# prc1000.net
KiCad netlist of a schematic drawn in EAGLE
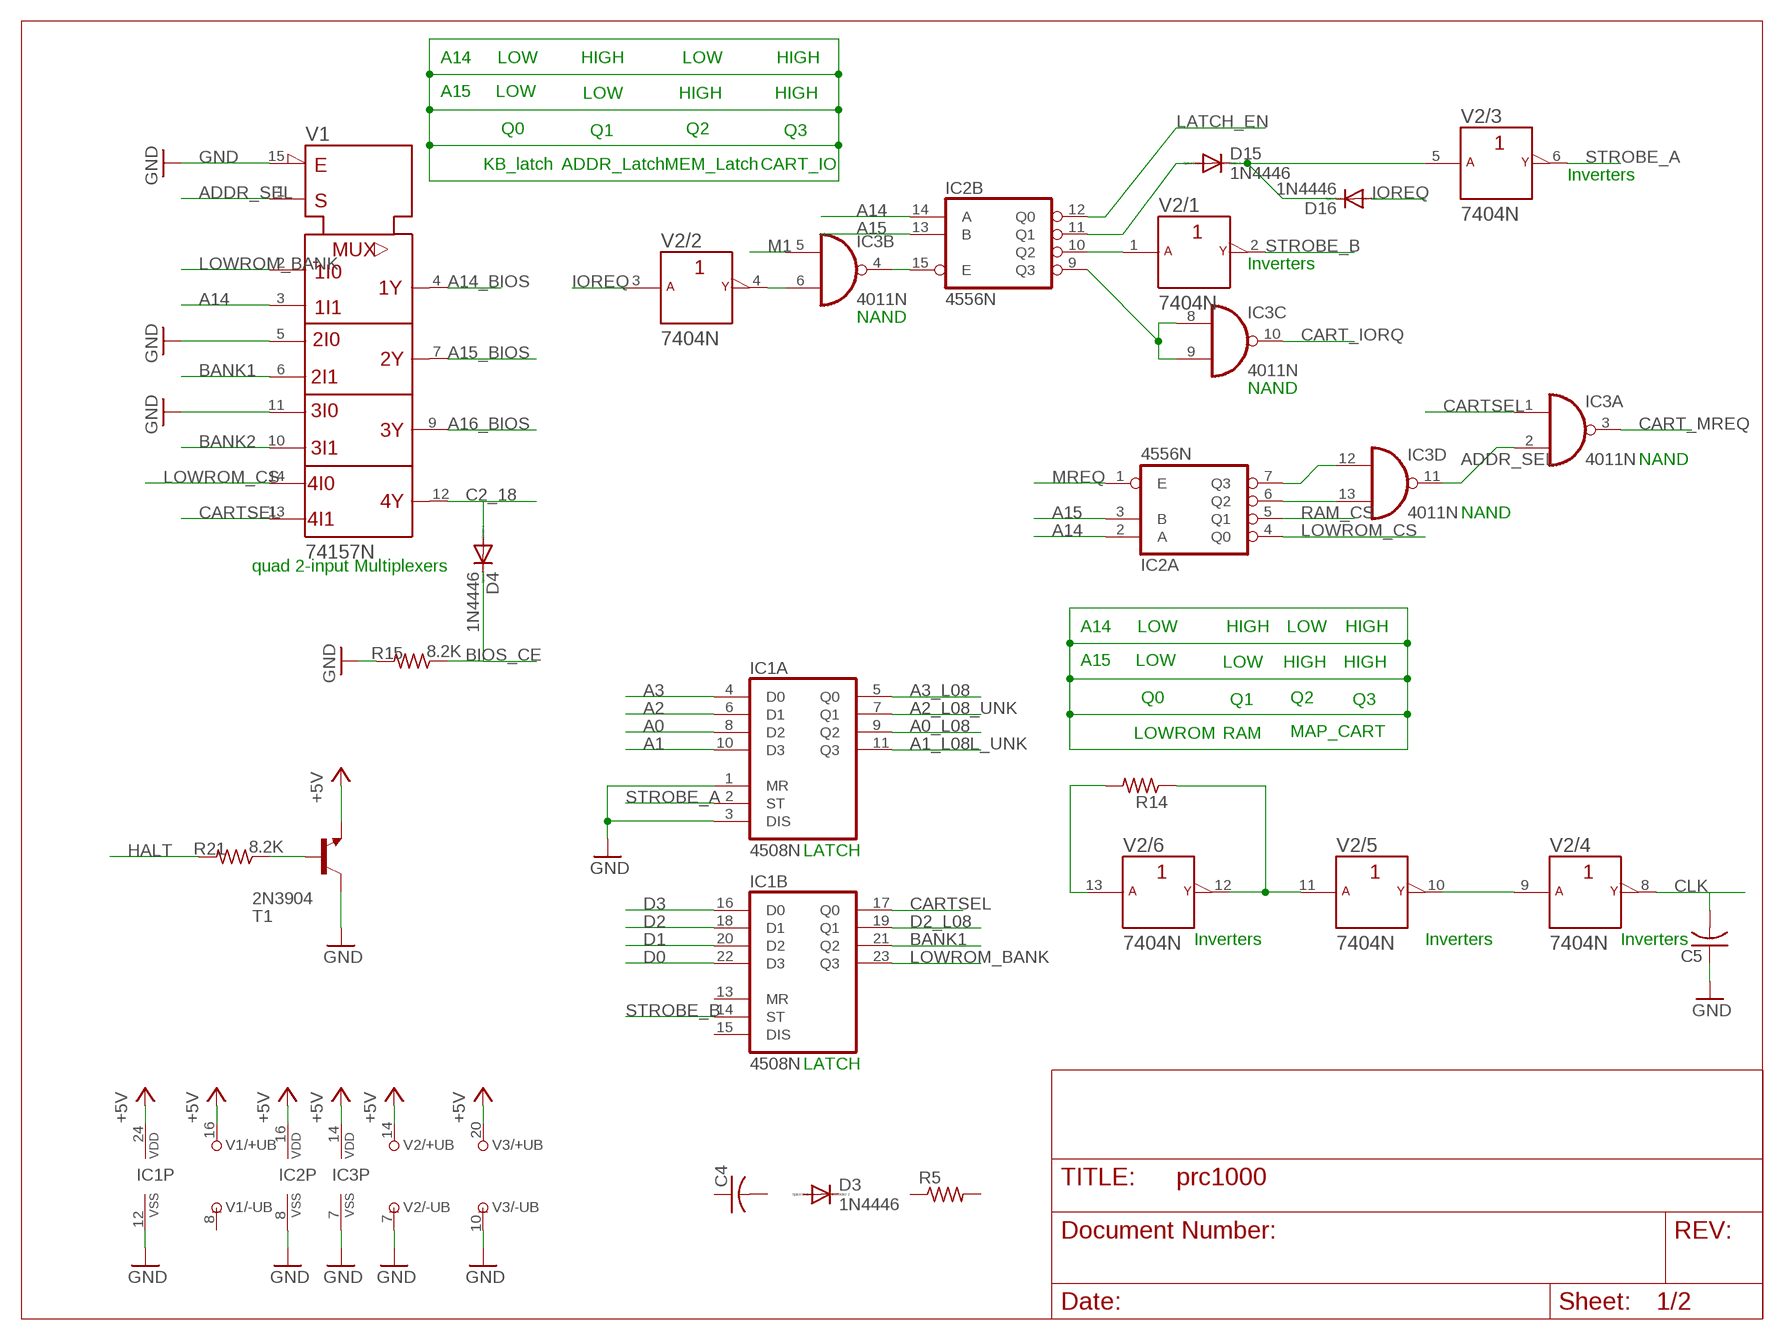
[diagram p0: schematic, sheet 1]
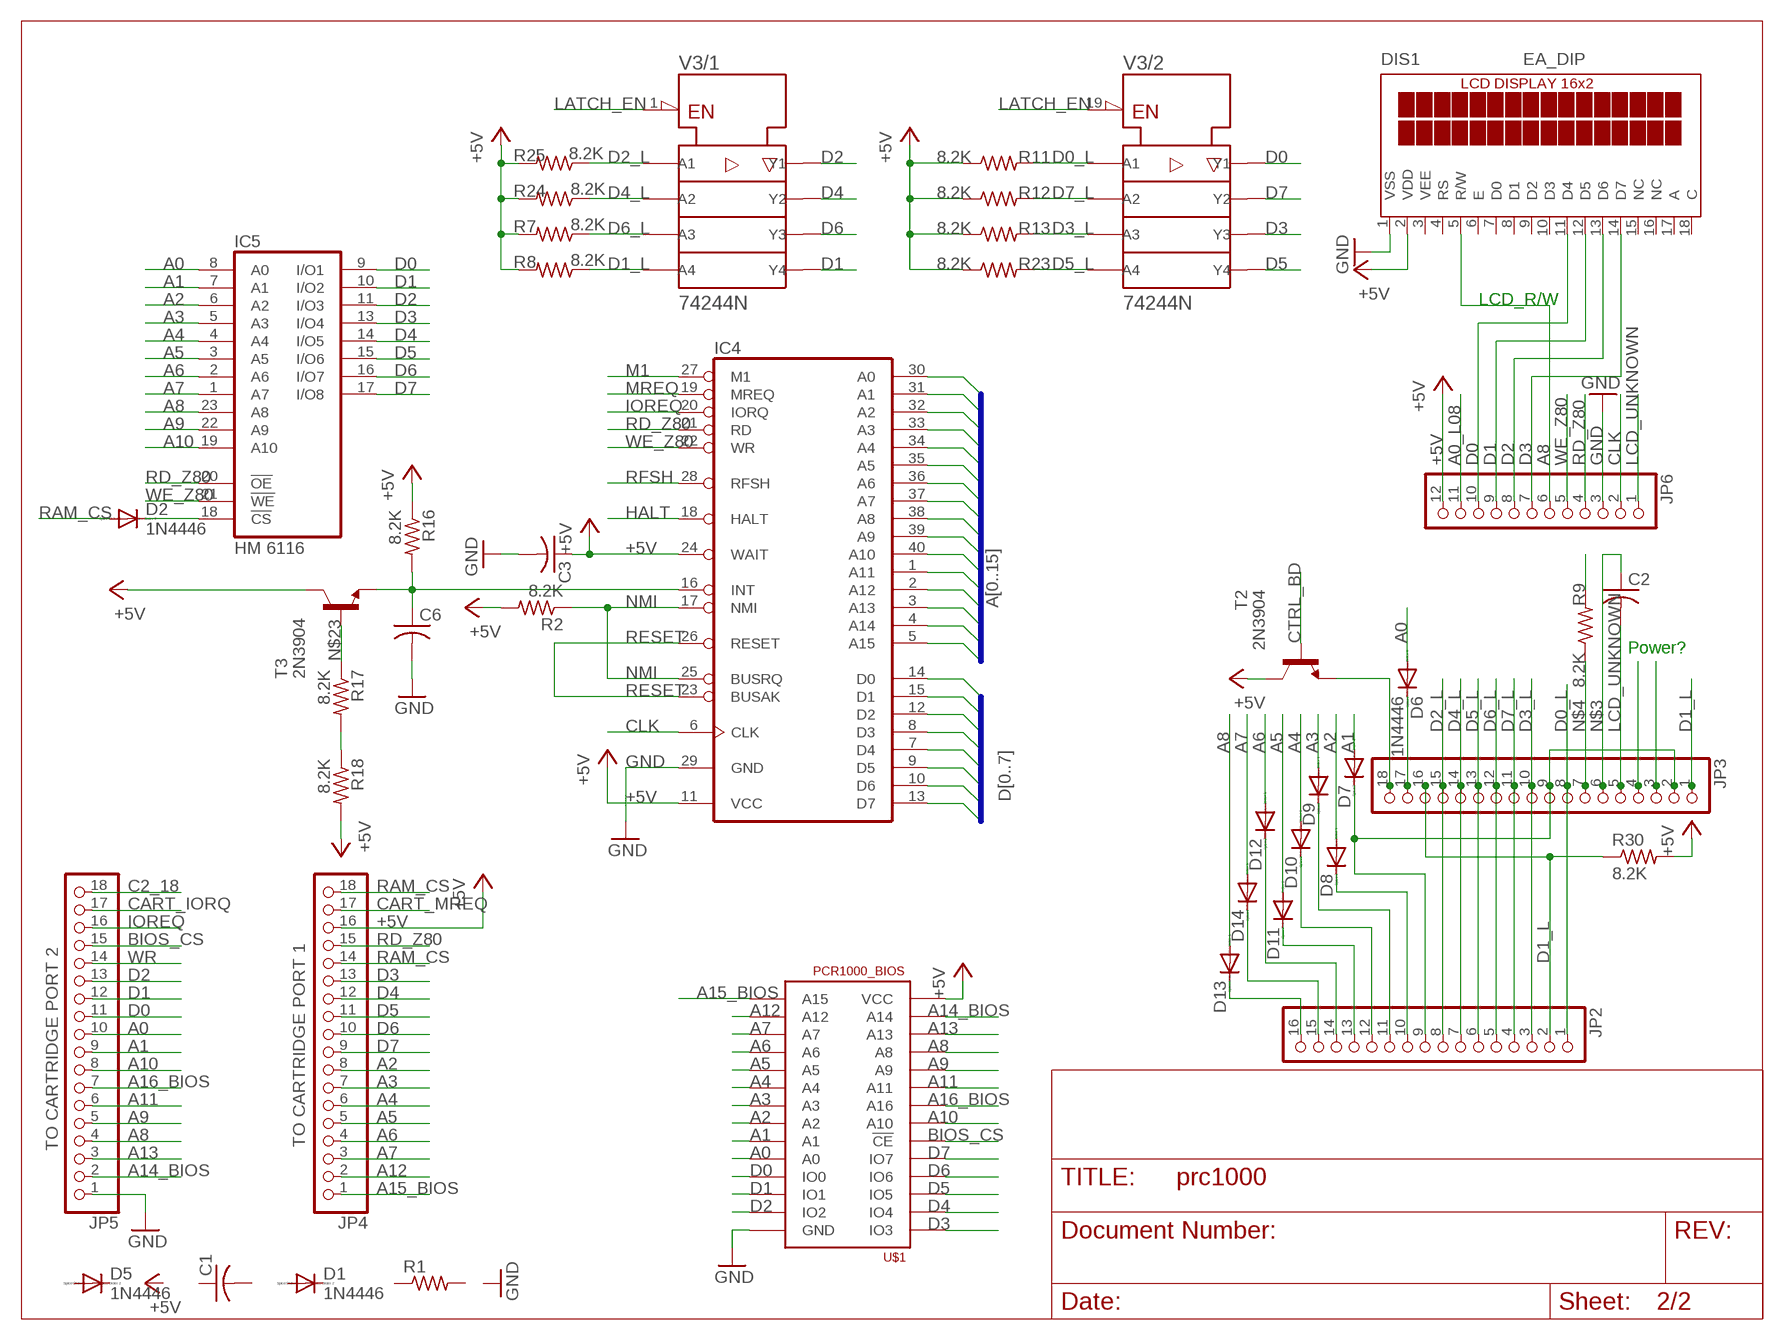
[diagram p1: schematic, sheet 2]

(export (version "E")
  (design (tool "Eeschema 10.0.6"))
  (components
    (comp (ref "C1")
      (value "C-US050-030X075")
      (footprint "eagle-import:C050-030X075")
      (libsource (lib "eagle-import") (part "C-US050-030X075"))
    )
    (comp (ref "C2")
      (value "C-US050-030X075")
      (footprint "eagle-import:C050-030X075")
      (libsource (lib "eagle-import") (part "C-US050-030X075"))
    )
    (comp (ref "C3")
      (value "C-US050-030X075")
      (footprint "eagle-import:C050-030X075")
      (libsource (lib "eagle-import") (part "C-US050-030X075"))
    )
    (comp (ref "C6")
      (value "C-US050-030X075")
      (footprint "eagle-import:C050-030X075")
      (libsource (lib "eagle-import") (part "C-US050-030X075"))
    )
    (comp (ref "D1")
      (value "1N4446")
      (footprint "eagle-import:DO35-10")
      (libsource (lib "eagle-import") (part "1N4446"))
    )
    (comp (ref "D2")
      (value "1N4446")
      (footprint "eagle-import:DO35-10")
      (libsource (lib "eagle-import") (part "1N4446"))
    )
    (comp (ref "D5")
      (value "1N4446")
      (footprint "eagle-import:DO35-10")
      (libsource (lib "eagle-import") (part "1N4446"))
    )
    (comp (ref "D6")
      (value "1N4446")
      (footprint "eagle-import:DO35-10")
      (libsource (lib "eagle-import") (part "1N4446"))
    )
    (comp (ref "D7")
      (value "1N4446")
      (footprint "eagle-import:DO35-10")
      (libsource (lib "eagle-import") (part "1N4446"))
    )
    (comp (ref "D8")
      (value "1N4446")
      (footprint "eagle-import:DO35-10")
      (libsource (lib "eagle-import") (part "1N4446"))
    )
    (comp (ref "D9")
      (value "1N4446")
      (footprint "eagle-import:DO35-10")
      (libsource (lib "eagle-import") (part "1N4446"))
    )
    (comp (ref "D10")
      (value "1N4446")
      (footprint "eagle-import:DO35-10")
      (libsource (lib "eagle-import") (part "1N4446"))
    )
    (comp (ref "D11")
      (value "1N4446")
      (footprint "eagle-import:DO35-10")
      (libsource (lib "eagle-import") (part "1N4446"))
    )
    (comp (ref "D12")
      (value "1N4446")
      (footprint "eagle-import:DO35-10")
      (libsource (lib "eagle-import") (part "1N4446"))
    )
    (comp (ref "D13")
      (value "1N4446")
      (footprint "eagle-import:DO35-10")
      (libsource (lib "eagle-import") (part "1N4446"))
    )
    (comp (ref "D14")
      (value "1N4446")
      (footprint "eagle-import:DO35-10")
      (libsource (lib "eagle-import") (part "1N4446"))
    )
    (comp (ref "DIS1")
      (value "EA_DIP")
      (footprint "eagle-import:EA_DIP")
      (libsource (lib "eagle-import") (part "EA_DIP"))
    )
    (comp (ref "IC4")
      (value "Z80CPU")
      (footprint "eagle-import:DIL40")
      (libsource (lib "eagle-import") (part "Z80CPU"))
    )
    (comp (ref "IC5")
      (value "HM 6116")
      (footprint "eagle-import:DIL24-6")
      (libsource (lib "eagle-import") (part "6116P"))
    )
    (comp (ref "JP2")
      (value "PINHD-1X16")
      (footprint "eagle-import:1X16")
      (libsource (lib "eagle-import") (part "PINHD-1X16"))
    )
    (comp (ref "JP3")
      (value "PINHD-1X18")
      (footprint "eagle-import:1X18")
      (libsource (lib "eagle-import") (part "PINHD-1X18"))
    )
    (comp (ref "JP4")
      (value "TO CARTRIDGE PORT 1")
      (footprint "eagle-import:1X18")
      (libsource (lib "eagle-import") (part "PINHD-1X18"))
    )
    (comp (ref "JP5")
      (value "TO CARTRIDGE PORT 2")
      (footprint "eagle-import:1X18")
      (libsource (lib "eagle-import") (part "PINHD-1X18"))
    )
    (comp (ref "JP6")
      (value "PINHD-1X12")
      (footprint "eagle-import:1X12")
      (libsource (lib "eagle-import") (part "PINHD-1X12"))
    )
    (comp (ref "R1")
      (value "R-US_0207/10")
      (footprint "eagle-import:0207_10")
      (libsource (lib "eagle-import") (part "R-US_0207/10"))
    )
    (comp (ref "R2")
      (value "8.2K")
      (footprint "eagle-import:0207_10")
      (libsource (lib "eagle-import") (part "R-US_0207/10"))
    )
    (comp (ref "R7")
      (value "8.2K")
      (footprint "eagle-import:0207_10")
      (libsource (lib "eagle-import") (part "R-US_0207/10"))
    )
    (comp (ref "R8")
      (value "8.2K")
      (footprint "eagle-import:0207_10")
      (libsource (lib "eagle-import") (part "R-US_0207/10"))
    )
    (comp (ref "R9")
      (value "8.2K")
      (footprint "eagle-import:0207_10")
      (libsource (lib "eagle-import") (part "R-US_0207/10"))
    )
    (comp (ref "R11")
      (value "8.2K")
      (footprint "eagle-import:0207_10")
      (libsource (lib "eagle-import") (part "R-US_0207/10"))
    )
    (comp (ref "R12")
      (value "8.2K")
      (footprint "eagle-import:0207_10")
      (libsource (lib "eagle-import") (part "R-US_0207/10"))
    )
    (comp (ref "R13")
      (value "8.2K")
      (footprint "eagle-import:0207_10")
      (libsource (lib "eagle-import") (part "R-US_0207/10"))
    )
    (comp (ref "R16")
      (value "8.2K")
      (footprint "eagle-import:0207_10")
      (libsource (lib "eagle-import") (part "R-US_0207/10"))
    )
    (comp (ref "R17")
      (value "8.2K")
      (footprint "eagle-import:0207_10")
      (libsource (lib "eagle-import") (part "R-US_0207/10"))
    )
    (comp (ref "R18")
      (value "8.2K")
      (footprint "eagle-import:0207_10")
      (libsource (lib "eagle-import") (part "R-US_0207/10"))
    )
    (comp (ref "R23")
      (value "8.2K")
      (footprint "eagle-import:0207_10")
      (libsource (lib "eagle-import") (part "R-US_0207/10"))
    )
    (comp (ref "R24")
      (value "8.2K")
      (footprint "eagle-import:0207_10")
      (libsource (lib "eagle-import") (part "R-US_0207/10"))
    )
    (comp (ref "R25")
      (value "8.2K")
      (footprint "eagle-import:0207_10")
      (libsource (lib "eagle-import") (part "R-US_0207/10"))
    )
    (comp (ref "R30")
      (value "8.2K")
      (footprint "eagle-import:0207_10")
      (libsource (lib "eagle-import") (part "R-US_0207/10"))
    )
    (comp (ref "T2")
      (value "2N3904")
      (footprint "eagle-import:TO92")
      (libsource (lib "eagle-import") (part "2N3904"))
    )
    (comp (ref "T3")
      (value "2N3904")
      (footprint "eagle-import:TO92")
      (libsource (lib "eagle-import") (part "2N3904"))
    )
    (comp (ref "U$1")
      (value "PCR1000_BIOS")
      (footprint "eagle-import:DIL28-6")
      (libsource (lib "eagle-import") (part "PCR1000_BIOS"))
    )
    (comp (ref "V3")
      (value "74244N")
      (footprint "eagle-import:DIL20")
      (libsource (lib "eagle-import") (part "74244N"))
    )
    (comp (ref "C4")
      (value "C-US050-030X075")
      (footprint "eagle-import:C050-030X075")
      (libsource (lib "eagle-import") (part "C-US050-030X075"))
    )
    (comp (ref "C5")
      (value "C-US050-030X075")
      (footprint "eagle-import:C050-030X075")
      (libsource (lib "eagle-import") (part "C-US050-030X075"))
    )
    (comp (ref "D3")
      (value "1N4446")
      (footprint "eagle-import:DO35-10")
      (libsource (lib "eagle-import") (part "1N4446"))
    )
    (comp (ref "D4")
      (value "1N4446")
      (footprint "eagle-import:DO35-10")
      (libsource (lib "eagle-import") (part "1N4446"))
    )
    (comp (ref "D15")
      (value "1N4446")
      (footprint "eagle-import:DO35-10")
      (libsource (lib "eagle-import") (part "1N4446"))
    )
    (comp (ref "D16")
      (value "1N4446")
      (footprint "eagle-import:DO35-10")
      (libsource (lib "eagle-import") (part "1N4446"))
    )
    (comp (ref "IC1")
      (value "4508N")
      (footprint "eagle-import:DIL24-6")
      (libsource (lib "eagle-import") (part "4508N"))
    )
    (comp (ref "IC2")
      (value "4556N")
      (footprint "eagle-import:DIL16")
      (libsource (lib "eagle-import") (part "4556N"))
    )
    (comp (ref "IC3")
      (value "4011N")
      (footprint "eagle-import:DIL14")
      (libsource (lib "eagle-import") (part "4011N"))
    )
    (comp (ref "R5")
      (value "R-US_0207/10")
      (footprint "eagle-import:0207_10")
      (libsource (lib "eagle-import") (part "R-US_0207/10"))
    )
    (comp (ref "R14")
      (value "R-US_0207/10")
      (footprint "eagle-import:0207_10")
      (libsource (lib "eagle-import") (part "R-US_0207/10"))
    )
    (comp (ref "R15")
      (value "8.2K")
      (footprint "eagle-import:0207_10")
      (libsource (lib "eagle-import") (part "R-US_0207/10"))
    )
    (comp (ref "R21")
      (value "8.2K")
      (footprint "eagle-import:0207_10")
      (libsource (lib "eagle-import") (part "R-US_0207/10"))
    )
    (comp (ref "T1")
      (value "2N3904")
      (footprint "eagle-import:TO92")
      (libsource (lib "eagle-import") (part "2N3904"))
    )
    (comp (ref "V1")
      (value "74157N")
      (footprint "eagle-import:DIL16")
      (libsource (lib "eagle-import") (part "74157N"))
    )
    (comp (ref "V2")
      (value "7404N")
      (footprint "eagle-import:DIL14")
      (libsource (lib "eagle-import") (part "7404N"))
    )
  )
  (nets
    (net (code "1") (name "+5V") (class "Default")
      (node (ref "C3") (pin "1") (pinfunction "1_1") (pintype "passive"))
      (node (ref "DIS1") (pin "2") (pinfunction "VDD_2") (pintype "power_in"))
      (node (ref "IC1") (pin "24") (pinfunction "VDD_24") (pintype "power_in"))
      (node (ref "IC2") (pin "16") (pinfunction "VDD_16") (pintype "power_in"))
      (node (ref "IC3") (pin "14") (pinfunction "VDD_14") (pintype "power_in"))
      (node (ref "IC4") (pin "11") (pinfunction "VCC_11") (pintype "power_in"))
      (node (ref "IC4") (pin "24") (pinfunction "WAIT_24") (pintype "input"))
      (node (ref "JP4") (pin "16") (pinfunction "16_16") (pintype "passive"))
      (node (ref "JP6") (pin "12") (pinfunction "12_12") (pintype "passive"))
      (node (ref "R11") (pin "1") (pinfunction "1_1") (pintype "passive"))
      (node (ref "R12") (pin "1") (pinfunction "1_1") (pintype "passive"))
      (node (ref "R13") (pin "1") (pinfunction "1_1") (pintype "passive"))
      (node (ref "R16") (pin "1") (pinfunction "1_1") (pintype "passive"))
      (node (ref "R18") (pin "2") (pinfunction "2_2") (pintype "passive"))
      (node (ref "R2") (pin "2") (pinfunction "2_2") (pintype "passive"))
      (node (ref "R23") (pin "1") (pinfunction "1_1") (pintype "passive"))
      (node (ref "R24") (pin "2") (pinfunction "2_2") (pintype "passive"))
      (node (ref "R25") (pin "2") (pinfunction "2_2") (pintype "passive"))
      (node (ref "R30") (pin "2") (pinfunction "2_2") (pintype "passive"))
      (node (ref "R7") (pin "2") (pinfunction "2_2") (pintype "passive"))
      (node (ref "R8") (pin "2") (pinfunction "2_2") (pintype "passive"))
      (node (ref "T1") (pin "3") (pinfunction "E_3") (pintype "passive"))
      (node (ref "T2") (pin "1") (pinfunction "C_1") (pintype "passive"))
      (node (ref "T3") (pin "1") (pinfunction "C_1") (pintype "passive"))
      (node (ref "U$1") (pin "28") (pinfunction "VCC_28") (pintype "bidirectional"))
      (node (ref "V1") (pin "16") (pinfunction "+UB_16") (pintype "power_in"))
      (node (ref "V2") (pin "14") (pinfunction "+UB_14") (pintype "power_in"))
      (node (ref "V3") (pin "20") (pinfunction "+UB_20") (pintype "power_in"))
    )
    (net (code "2") (name "-UB") (class "Default")
      (node (ref "V1") (pin "8") (pinfunction "-UB_8") (pintype "power_in"))
    )
    (net (code "5") (name "A0") (class "Default")
      (node (ref "D6") (pin "A") (pinfunction "A_A") (pintype "passive"))
      (node (ref "IC1") (pin "8") (pinfunction "D2_8") (pintype "input"))
      (node (ref "IC4") (pin "30") (pinfunction "A0_30") (pintype "output"))
      (node (ref "IC5") (pin "8") (pinfunction "A0_8") (pintype "input"))
      (node (ref "JP5") (pin "10") (pinfunction "10_10") (pintype "passive"))
      (node (ref "U$1") (pin "10") (pinfunction "A0_10") (pintype "bidirectional"))
    )
    (net (code "6") (name "A0_L08") (class "Default")
      (node (ref "IC1") (pin "9") (pinfunction "Q2_9") (pintype "output"))
      (node (ref "JP6") (pin "11") (pinfunction "11_11") (pintype "passive"))
    )
    (net (code "7") (name "A1") (class "Default")
      (node (ref "D7") (pin "A") (pinfunction "A_A") (pintype "passive"))
      (node (ref "IC1") (pin "10") (pinfunction "D3_10") (pintype "input"))
      (node (ref "IC4") (pin "31") (pinfunction "A1_31") (pintype "output"))
      (node (ref "IC5") (pin "7") (pinfunction "A1_7") (pintype "input"))
      (node (ref "JP5") (pin "9") (pinfunction "9_9") (pintype "passive"))
      (node (ref "U$1") (pin "9") (pinfunction "A1_9") (pintype "bidirectional"))
    )
    (net (code "8") (name "A1_L08L_UNK") (class "Default")
      (node (ref "IC1") (pin "11") (pinfunction "Q3_11") (pintype "output"))
    )
    (net (code "9") (name "A2") (class "Default")
      (node (ref "D8") (pin "A") (pinfunction "A_A") (pintype "passive"))
      (node (ref "IC1") (pin "6") (pinfunction "D1_6") (pintype "input"))
      (node (ref "IC4") (pin "32") (pinfunction "A2_32") (pintype "output"))
      (node (ref "IC5") (pin "6") (pinfunction "A2_6") (pintype "input"))
      (node (ref "JP4") (pin "8") (pinfunction "8_8") (pintype "passive"))
      (node (ref "U$1") (pin "8") (pinfunction "A2_8") (pintype "bidirectional"))
    )
    (net (code "10") (name "A2_L08_UNK") (class "Default")
      (node (ref "IC1") (pin "7") (pinfunction "Q1_7") (pintype "output"))
    )
    (net (code "11") (name "A3") (class "Default")
      (node (ref "D9") (pin "A") (pinfunction "A_A") (pintype "passive"))
      (node (ref "IC1") (pin "4") (pinfunction "D0_4") (pintype "input"))
      (node (ref "IC4") (pin "33") (pinfunction "A3_33") (pintype "output"))
      (node (ref "IC5") (pin "5") (pinfunction "A3_5") (pintype "input"))
      (node (ref "JP4") (pin "7") (pinfunction "7_7") (pintype "passive"))
      (node (ref "U$1") (pin "7") (pinfunction "A3_7") (pintype "bidirectional"))
    )
    (net (code "12") (name "A3_L08") (class "Default")
      (node (ref "IC1") (pin "5") (pinfunction "Q0_5") (pintype "output"))
    )
    (net (code "13") (name "A4") (class "Default")
      (node (ref "D10") (pin "A") (pinfunction "A_A") (pintype "passive"))
      (node (ref "IC4") (pin "34") (pinfunction "A4_34") (pintype "output"))
      (node (ref "IC5") (pin "4") (pinfunction "A4_4") (pintype "input"))
      (node (ref "JP4") (pin "6") (pinfunction "6_6") (pintype "passive"))
      (node (ref "U$1") (pin "6") (pinfunction "A4_6") (pintype "bidirectional"))
    )
    (net (code "14") (name "A5") (class "Default")
      (node (ref "D11") (pin "A") (pinfunction "A_A") (pintype "passive"))
      (node (ref "IC4") (pin "35") (pinfunction "A5_35") (pintype "output"))
      (node (ref "IC5") (pin "3") (pinfunction "A5_3") (pintype "input"))
      (node (ref "JP4") (pin "5") (pinfunction "5_5") (pintype "passive"))
      (node (ref "U$1") (pin "5") (pinfunction "A5_5") (pintype "bidirectional"))
    )
    (net (code "15") (name "A6") (class "Default")
      (node (ref "D12") (pin "A") (pinfunction "A_A") (pintype "passive"))
      (node (ref "IC4") (pin "36") (pinfunction "A6_36") (pintype "output"))
      (node (ref "IC5") (pin "2") (pinfunction "A6_2") (pintype "input"))
      (node (ref "JP4") (pin "4") (pinfunction "4_4") (pintype "passive"))
      (node (ref "U$1") (pin "4") (pinfunction "A6_4") (pintype "bidirectional"))
    )
    (net (code "16") (name "A7") (class "Default")
      (node (ref "D14") (pin "A") (pinfunction "A_A") (pintype "passive"))
      (node (ref "IC4") (pin "37") (pinfunction "A7_37") (pintype "output"))
      (node (ref "IC5") (pin "1") (pinfunction "A7_1") (pintype "input"))
      (node (ref "JP4") (pin "3") (pinfunction "3_3") (pintype "passive"))
      (node (ref "U$1") (pin "3") (pinfunction "A7_3") (pintype "bidirectional"))
    )
    (net (code "17") (name "A8") (class "Default")
      (node (ref "D13") (pin "A") (pinfunction "A_A") (pintype "passive"))
      (node (ref "DIS1") (pin "5") (pinfunction "R/W_5") (pintype "input"))
      (node (ref "IC4") (pin "38") (pinfunction "A8_38") (pintype "output"))
      (node (ref "IC5") (pin "23") (pinfunction "A8_23") (pintype "input"))
      (node (ref "JP5") (pin "4") (pinfunction "4_4") (pintype "passive"))
      (node (ref "JP6") (pin "6") (pinfunction "6_6") (pintype "passive"))
      (node (ref "U$1") (pin "25") (pinfunction "A8_25") (pintype "bidirectional"))
    )
    (net (code "18") (name "A9") (class "Default")
      (node (ref "IC4") (pin "39") (pinfunction "A9_39") (pintype "output"))
      (node (ref "IC5") (pin "22") (pinfunction "A9_22") (pintype "input"))
      (node (ref "JP5") (pin "5") (pinfunction "5_5") (pintype "passive"))
      (node (ref "U$1") (pin "24") (pinfunction "A9_24") (pintype "bidirectional"))
    )
    (net (code "19") (name "A10") (class "Default")
      (node (ref "IC4") (pin "40") (pinfunction "A10_40") (pintype "output"))
      (node (ref "IC5") (pin "19") (pinfunction "A10_19") (pintype "input"))
      (node (ref "JP5") (pin "8") (pinfunction "8_8") (pintype "passive"))
      (node (ref "U$1") (pin "21") (pinfunction "A10_21") (pintype "bidirectional"))
    )
    (net (code "20") (name "A11") (class "Default")
      (node (ref "IC4") (pin "1") (pinfunction "A11_1") (pintype "output"))
      (node (ref "JP5") (pin "6") (pinfunction "6_6") (pintype "passive"))
      (node (ref "U$1") (pin "23") (pinfunction "A11_23") (pintype "bidirectional"))
    )
    (net (code "21") (name "A12") (class "Default")
      (node (ref "IC4") (pin "2") (pinfunction "A12_2") (pintype "output"))
      (node (ref "JP4") (pin "2") (pinfunction "2_2") (pintype "passive"))
      (node (ref "U$1") (pin "2") (pinfunction "A12_2") (pintype "bidirectional"))
    )
    (net (code "22") (name "A13") (class "Default")
      (node (ref "IC4") (pin "3") (pinfunction "A13_3") (pintype "output"))
      (node (ref "JP5") (pin "3") (pinfunction "3_3") (pintype "passive"))
      (node (ref "U$1") (pin "26") (pinfunction "A13_26") (pintype "bidirectional"))
    )
    (net (code "23") (name "A14") (class "Default")
      (node (ref "IC2") (pin "14") (pinfunction "A_14") (pintype "input"))
      (node (ref "IC2") (pin "2") (pinfunction "A_2") (pintype "input"))
      (node (ref "IC4") (pin "4") (pinfunction "A14_4") (pintype "output"))
      (node (ref "V1") (pin "3") (pinfunction "1B_3") (pintype "input"))
    )
    (net (code "24") (name "A14_BIOS") (class "Default")
      (node (ref "JP5") (pin "2") (pinfunction "2_2") (pintype "passive"))
      (node (ref "U$1") (pin "27") (pinfunction "A14_27") (pintype "bidirectional"))
      (node (ref "V1") (pin "4") (pinfunction "1Y_4") (pintype "output"))
    )
    (net (code "25") (name "A15") (class "Default")
      (node (ref "IC2") (pin "13") (pinfunction "B_13") (pintype "input"))
      (node (ref "IC2") (pin "3") (pinfunction "B_3") (pintype "input"))
      (node (ref "IC4") (pin "5") (pinfunction "A15_5") (pintype "output"))
    )
    (net (code "26") (name "A15_BIOS") (class "Default")
      (node (ref "JP4") (pin "1") (pinfunction "1_1") (pintype "passive"))
      (node (ref "U$1") (pin "1") (pinfunction "A15_1") (pintype "bidirectional"))
      (node (ref "V1") (pin "7") (pinfunction "2Y_7") (pintype "output"))
    )
    (net (code "27") (name "A16_BIOS") (class "Default")
      (node (ref "JP5") (pin "7") (pinfunction "7_7") (pintype "passive"))
      (node (ref "U$1") (pin "22") (pinfunction "A16_22") (pintype "bidirectional"))
      (node (ref "V1") (pin "9") (pinfunction "3Y_9") (pintype "output"))
    )
    (net (code "28") (name "ADDR_SEL") (class "Default")
      (node (ref "IC3") (pin "11") (pinfunction "O_11") (pintype "output"))
      (node (ref "IC3") (pin "2") (pinfunction "I1_2") (pintype "input"))
      (node (ref "V1") (pin "1") (pinfunction "~{A}/B_1") (pintype "input"))
    )
    (net (code "29") (name "BANK1") (class "Default")
      (node (ref "IC1") (pin "21") (pinfunction "Q2_21") (pintype "output"))
      (node (ref "V1") (pin "6") (pinfunction "2B_6") (pintype "input"))
    )
    (net (code "30") (name "BANK2") (class "Default")
      (node (ref "V1") (pin "10") (pinfunction "3B_10") (pintype "input"))
    )
    (net (code "31") (name "BIOS_CE") (class "Default")
      (node (ref "D4") (pin "C") (pinfunction "C_C") (pintype "passive"))
      (node (ref "R15") (pin "1") (pinfunction "1_1") (pintype "passive"))
    )
    (net (code "32") (name "BIOS_CS") (class "Default")
      (node (ref "JP5") (pin "15") (pinfunction "15_15") (pintype "passive"))
      (node (ref "U$1") (pin "20") (pinfunction "~{CE}_20") (pintype "bidirectional"))
    )
    (net (code "33") (name "C2_18") (class "Default")
      (node (ref "D4") (pin "A") (pinfunction "A_A") (pintype "passive"))
      (node (ref "JP5") (pin "18") (pinfunction "18_18") (pintype "passive"))
      (node (ref "V1") (pin "12") (pinfunction "4Y_12") (pintype "output"))
    )
    (net (code "34") (name "CARTSEL") (class "Default")
      (node (ref "IC1") (pin "17") (pinfunction "Q0_17") (pintype "output"))
      (node (ref "IC3") (pin "1") (pinfunction "I0_1") (pintype "input"))
      (node (ref "V1") (pin "13") (pinfunction "4B_13") (pintype "input"))
    )
    (net (code "35") (name "CART_IORQ") (class "Default")
      (node (ref "IC3") (pin "10") (pinfunction "O_10") (pintype "output"))
      (node (ref "JP5") (pin "17") (pinfunction "17_17") (pintype "passive"))
    )
    (net (code "36") (name "CART_MREQ") (class "Default")
      (node (ref "IC3") (pin "3") (pinfunction "O_3") (pintype "output"))
      (node (ref "JP4") (pin "17") (pinfunction "17_17") (pintype "passive"))
    )
    (net (code "37") (name "CLK") (class "Default")
      (node (ref "C5") (pin "2") (pinfunction "2_2") (pintype "passive"))
      (node (ref "IC4") (pin "6") (pinfunction "CLK_6") (pintype "input"))
      (node (ref "JP6") (pin "2") (pinfunction "2_2") (pintype "passive"))
      (node (ref "V2") (pin "8") (pinfunction "Y_8") (pintype "output"))
    )
    (net (code "38") (name "CTRL_BD") (class "Default")
      (node (ref "T2") (pin "2") (pinfunction "B_2") (pintype "passive"))
    )
    (net (code "39") (name "D0") (class "Default")
      (node (ref "DIS1") (pin "11") (pinfunction "D4_11") (pintype "input"))
      (node (ref "IC1") (pin "22") (pinfunction "D3_22") (pintype "input"))
      (node (ref "IC4") (pin "14") (pinfunction "D0_14") (pintype "bidirectional"))
      (node (ref "IC5") (pin "9") (pinfunction "I/O1_9") (pintype "bidirectional"))
      (node (ref "JP5") (pin "11") (pinfunction "11_11") (pintype "passive"))
      (node (ref "JP6") (pin "10") (pinfunction "10_10") (pintype "passive"))
      (node (ref "U$1") (pin "11") (pinfunction "IO0_11") (pintype "bidirectional"))
      (node (ref "V3") (pin "9") (pinfunction "Y1_9") (pintype "tri_state"))
    )
    (net (code "40") (name "D0_L") (class "Default")
      (node (ref "JP2") (pin "1") (pinfunction "1_1") (pintype "passive"))
      (node (ref "JP3") (pin "8") (pinfunction "8_8") (pintype "passive"))
      (node (ref "R11") (pin "2") (pinfunction "2_2") (pintype "passive"))
      (node (ref "V3") (pin "11") (pinfunction "A1_11") (pintype "input"))
    )
    (net (code "41") (name "D1") (class "Default")
      (node (ref "DIS1") (pin "12") (pinfunction "D5_12") (pintype "input"))
      (node (ref "IC1") (pin "20") (pinfunction "D2_20") (pintype "input"))
      (node (ref "IC4") (pin "15") (pinfunction "D1_15") (pintype "bidirectional"))
      (node (ref "IC5") (pin "10") (pinfunction "I/O2_10") (pintype "bidirectional"))
      (node (ref "JP5") (pin "12") (pinfunction "12_12") (pintype "passive"))
      (node (ref "JP6") (pin "9") (pinfunction "9_9") (pintype "passive"))
      (node (ref "U$1") (pin "12") (pinfunction "IO1_12") (pintype "bidirectional"))
      (node (ref "V3") (pin "12") (pinfunction "Y4_12") (pintype "tri_state"))
    )
    (net (code "42") (name "D1_L") (class "Default")
      (node (ref "JP2") (pin "2") (pinfunction "2_2") (pintype "passive"))
      (node (ref "JP3") (pin "1") (pinfunction "1_1") (pintype "passive"))
      (node (ref "JP3") (pin "16") (pinfunction "16_16") (pintype "passive"))
      (node (ref "R30") (pin "1") (pinfunction "1_1") (pintype "passive"))
      (node (ref "R8") (pin "1") (pinfunction "1_1") (pintype "passive"))
      (node (ref "V3") (pin "8") (pinfunction "A4_8") (pintype "input"))
    )
    (net (code "43") (name "D2") (class "Default")
      (node (ref "DIS1") (pin "13") (pinfunction "D6_13") (pintype "input"))
      (node (ref "IC1") (pin "18") (pinfunction "D1_18") (pintype "input"))
      (node (ref "IC4") (pin "12") (pinfunction "D2_12") (pintype "bidirectional"))
      (node (ref "IC5") (pin "11") (pinfunction "I/O3_11") (pintype "bidirectional"))
      (node (ref "JP5") (pin "13") (pinfunction "13_13") (pintype "passive"))
      (node (ref "JP6") (pin "8") (pinfunction "8_8") (pintype "passive"))
      (node (ref "U$1") (pin "13") (pinfunction "IO2_13") (pintype "bidirectional"))
      (node (ref "V3") (pin "18") (pinfunction "Y1_18") (pintype "tri_state"))
    )
    (net (code "44") (name "D2_L") (class "Default")
      (node (ref "JP2") (pin "8") (pinfunction "8_8") (pintype "passive"))
      (node (ref "JP3") (pin "15") (pinfunction "15_15") (pintype "passive"))
      (node (ref "R25") (pin "1") (pinfunction "1_1") (pintype "passive"))
      (node (ref "V3") (pin "2") (pinfunction "A1_2") (pintype "input"))
    )
    (net (code "45") (name "D2_L08") (class "Default")
      (node (ref "IC1") (pin "19") (pinfunction "Q1_19") (pintype "output"))
    )
    (net (code "46") (name "D3") (class "Default")
      (node (ref "DIS1") (pin "14") (pinfunction "D7_14") (pintype "input"))
      (node (ref "IC1") (pin "16") (pinfunction "D0_16") (pintype "input"))
      (node (ref "IC4") (pin "8") (pinfunction "D3_8") (pintype "bidirectional"))
      (node (ref "IC5") (pin "13") (pinfunction "I/O4_13") (pintype "bidirectional"))
      (node (ref "JP4") (pin "13") (pinfunction "13_13") (pintype "passive"))
      (node (ref "JP6") (pin "7") (pinfunction "7_7") (pintype "passive"))
      (node (ref "U$1") (pin "15") (pinfunction "IO3_15") (pintype "bidirectional"))
      (node (ref "V3") (pin "5") (pinfunction "Y3_5") (pintype "tri_state"))
    )
    (net (code "47") (name "D3_L") (class "Default")
      (node (ref "JP2") (pin "3") (pinfunction "3_3") (pintype "passive"))
      (node (ref "JP3") (pin "10") (pinfunction "10_10") (pintype "passive"))
      (node (ref "R13") (pin "2") (pinfunction "2_2") (pintype "passive"))
      (node (ref "V3") (pin "15") (pinfunction "A3_15") (pintype "input"))
    )
    (net (code "48") (name "D4") (class "Default")
      (node (ref "IC4") (pin "7") (pinfunction "D4_7") (pintype "bidirectional"))
      (node (ref "IC5") (pin "14") (pinfunction "I/O5_14") (pintype "bidirectional"))
      (node (ref "JP4") (pin "12") (pinfunction "12_12") (pintype "passive"))
      (node (ref "U$1") (pin "16") (pinfunction "IO4_16") (pintype "bidirectional"))
      (node (ref "V3") (pin "16") (pinfunction "Y2_16") (pintype "tri_state"))
    )
    (net (code "49") (name "D4_L") (class "Default")
      (node (ref "JP2") (pin "7") (pinfunction "7_7") (pintype "passive"))
      (node (ref "JP3") (pin "14") (pinfunction "14_14") (pintype "passive"))
      (node (ref "R24") (pin "1") (pinfunction "1_1") (pintype "passive"))
      (node (ref "V3") (pin "4") (pinfunction "A2_4") (pintype "input"))
    )
    (net (code "50") (name "D5") (class "Default")
      (node (ref "IC4") (pin "9") (pinfunction "D5_9") (pintype "bidirectional"))
      (node (ref "IC5") (pin "15") (pinfunction "I/O6_15") (pintype "bidirectional"))
      (node (ref "JP4") (pin "11") (pinfunction "11_11") (pintype "passive"))
      (node (ref "U$1") (pin "17") (pinfunction "IO5_17") (pintype "bidirectional"))
      (node (ref "V3") (pin "3") (pinfunction "Y4_3") (pintype "tri_state"))
    )
    (net (code "51") (name "D5_L") (class "Default")
      (node (ref "JP2") (pin "6") (pinfunction "6_6") (pintype "passive"))
      (node (ref "JP3") (pin "13") (pinfunction "13_13") (pintype "passive"))
      (node (ref "R23") (pin "2") (pinfunction "2_2") (pintype "passive"))
      (node (ref "V3") (pin "17") (pinfunction "A4_17") (pintype "input"))
    )
    (net (code "52") (name "D6") (class "Default")
      (node (ref "IC4") (pin "10") (pinfunction "D6_10") (pintype "bidirectional"))
      (node (ref "IC5") (pin "16") (pinfunction "I/O7_16") (pintype "bidirectional"))
      (node (ref "JP4") (pin "10") (pinfunction "10_10") (pintype "passive"))
      (node (ref "U$1") (pin "18") (pinfunction "IO6_18") (pintype "bidirectional"))
      (node (ref "V3") (pin "14") (pinfunction "Y3_14") (pintype "tri_state"))
    )
    (net (code "53") (name "D6_L") (class "Default")
      (node (ref "JP2") (pin "5") (pinfunction "5_5") (pintype "passive"))
      (node (ref "JP3") (pin "12") (pinfunction "12_12") (pintype "passive"))
      (node (ref "R7") (pin "1") (pinfunction "1_1") (pintype "passive"))
      (node (ref "V3") (pin "6") (pinfunction "A3_6") (pintype "input"))
    )
    (net (code "54") (name "D7") (class "Default")
      (node (ref "IC4") (pin "13") (pinfunction "D7_13") (pintype "bidirectional"))
      (node (ref "IC5") (pin "17") (pinfunction "I/O8_17") (pintype "bidirectional"))
      (node (ref "JP4") (pin "9") (pinfunction "9_9") (pintype "passive"))
      (node (ref "U$1") (pin "19") (pinfunction "IO7_19") (pintype "bidirectional"))
      (node (ref "V3") (pin "7") (pinfunction "Y2_7") (pintype "tri_state"))
    )
    (net (code "55") (name "D7_L") (class "Default")
      (node (ref "JP2") (pin "4") (pinfunction "4_4") (pintype "passive"))
      (node (ref "JP3") (pin "11") (pinfunction "11_11") (pintype "passive"))
      (node (ref "R12") (pin "2") (pinfunction "2_2") (pintype "passive"))
      (node (ref "V3") (pin "13") (pinfunction "A2_13") (pintype "input"))
    )
    (net (code "56") (name "GND") (class "Default")
      (node (ref "C3") (pin "2") (pinfunction "2_2") (pintype "passive"))
      (node (ref "C5") (pin "1") (pinfunction "1_1") (pintype "passive"))
      (node (ref "C6") (pin "2") (pinfunction "2_2") (pintype "passive"))
      (node (ref "DIS1") (pin "1") (pinfunction "VSS_1") (pintype "power_in"))
      (node (ref "IC1") (pin "1") (pinfunction "MR_1") (pintype "input"))
      (node (ref "IC1") (pin "12") (pinfunction "VSS_12") (pintype "power_in"))
      (node (ref "IC1") (pin "3") (pinfunction "DIS_3") (pintype "input"))
      (node (ref "IC2") (pin "8") (pinfunction "VSS_8") (pintype "power_in"))
      (node (ref "IC3") (pin "7") (pinfunction "VSS_7") (pintype "power_in"))
      (node (ref "IC4") (pin "29") (pinfunction "GND_29") (pintype "power_in"))
      (node (ref "JP5") (pin "1") (pinfunction "1_1") (pintype "passive"))
      (node (ref "JP6") (pin "3") (pinfunction "3_3") (pintype "passive"))
      (node (ref "R15") (pin "2") (pinfunction "2_2") (pintype "passive"))
      (node (ref "T1") (pin "1") (pinfunction "C_1") (pintype "passive"))
      (node (ref "U$1") (pin "14") (pinfunction "GND_14") (pintype "bidirectional"))
      (node (ref "V1") (pin "11") (pinfunction "3A_11") (pintype "input"))
      (node (ref "V1") (pin "15") (pinfunction "~{G}_15") (pintype "input"))
      (node (ref "V1") (pin "5") (pinfunction "2A_5") (pintype "input"))
      (node (ref "V2") (pin "7") (pinfunction "-UB_7") (pintype "power_in"))
      (node (ref "V3") (pin "10") (pinfunction "-UB_10") (pintype "power_in"))
    )
    (net (code "57") (name "HALT") (class "Default")
      (node (ref "IC4") (pin "18") (pinfunction "HALT_18") (pintype "output"))
      (node (ref "R21") (pin "2") (pinfunction "2_2") (pintype "passive"))
    )
    (net (code "58") (name "IOREQ") (class "Default")
      (node (ref "D16") (pin "A") (pinfunction "A_A") (pintype "passive"))
      (node (ref "IC4") (pin "20") (pinfunction "IORQ_20") (pintype "output"))
      (node (ref "JP5") (pin "16") (pinfunction "16_16") (pintype "passive"))
      (node (ref "V2") (pin "3") (pinfunction "A_3") (pintype "input"))
    )
    (net (code "59") (name "LATCH_EN") (class "Default")
      (node (ref "IC2") (pin "12") (pinfunction "Q0_12") (pintype "output"))
      (node (ref "V3") (pin "1") (pinfunction "~{G}_1") (pintype "input"))
      (node (ref "V3") (pin "19") (pinfunction "~{G}_19") (pintype "input"))
    )
    (net (code "60") (name "LCD_UNKNOWN") (class "Default")
      (node (ref "C2") (pin "2") (pinfunction "2_2") (pintype "passive"))
      (node (ref "JP3") (pin "5") (pinfunction "5_5") (pintype "passive"))
      (node (ref "JP6") (pin "1") (pinfunction "1_1") (pintype "passive"))
    )
    (net (code "61") (name "LOWROM_BANK") (class "Default")
      (node (ref "IC1") (pin "23") (pinfunction "Q3_23") (pintype "output"))
      (node (ref "V1") (pin "2") (pinfunction "1A_2") (pintype "input"))
    )
    (net (code "62") (name "LOWROM_CS") (class "Default")
      (node (ref "IC2") (pin "4") (pinfunction "Q0_4") (pintype "output"))
      (node (ref "V1") (pin "14") (pinfunction "4A_14") (pintype "input"))
    )
    (net (code "63") (name "M1") (class "Default")
      (node (ref "IC3") (pin "5") (pinfunction "I0_5") (pintype "input"))
      (node (ref "IC4") (pin "27") (pinfunction "M1_27") (pintype "output"))
    )
    (net (code "64") (name "MREQ") (class "Default")
      (node (ref "IC2") (pin "1") (pinfunction "E_1") (pintype "input"))
      (node (ref "IC4") (pin "19") (pinfunction "MREQ_19") (pintype "output"))
    )
    (net (code "65") (name "N$3") (class "Default")
      (node (ref "C2") (pin "1") (pinfunction "1_1") (pintype "passive"))
      (node (ref "JP3") (pin "6") (pinfunction "6_6") (pintype "passive"))
    )
    (net (code "66") (name "N$4") (class "Default")
      (node (ref "JP3") (pin "7") (pinfunction "7_7") (pintype "passive"))
      (node (ref "R9") (pin "1") (pinfunction "1_1") (pintype "passive"))
    )
    (net (code "67") (name "N$23") (class "Default")
      (node (ref "R17") (pin "1") (pinfunction "1_1") (pintype "passive"))
      (node (ref "T3") (pin "2") (pinfunction "B_2") (pintype "passive"))
    )
    (net (code "68") (name "NMI") (class "Default")
      (node (ref "IC4") (pin "17") (pinfunction "NMI_17") (pintype "input"))
      (node (ref "IC4") (pin "25") (pinfunction "BUSRQ_25") (pintype "input"))
      (node (ref "R2") (pin "1") (pinfunction "1_1") (pintype "passive"))
    )
    (net (code "69") (name "Net-(D6-PadC)") (class "Default")
      (node (ref "D6") (pin "C") (pinfunction "C_C") (pintype "passive"))
      (node (ref "JP3") (pin "17") (pinfunction "17_17") (pintype "passive"))
    )
    (net (code "70") (name "Net-(D7-PadC)") (class "Default")
      (node (ref "D7") (pin "C") (pinfunction "C_C") (pintype "passive"))
      (node (ref "JP2") (pin "9") (pinfunction "9_9") (pintype "passive"))
      (node (ref "JP3") (pin "2") (pinfunction "2_2") (pintype "passive"))
      (node (ref "JP3") (pin "9") (pinfunction "9_9") (pintype "passive"))
    )
    (net (code "71") (name "Net-(D8-PadC)") (class "Default")
      (node (ref "D8") (pin "C") (pinfunction "C_C") (pintype "passive"))
      (node (ref "JP2") (pin "10") (pinfunction "10_10") (pintype "passive"))
    )
    (net (code "72") (name "Net-(D9-PadC)") (class "Default")
      (node (ref "D9") (pin "C") (pinfunction "C_C") (pintype "passive"))
      (node (ref "JP2") (pin "11") (pinfunction "11_11") (pintype "passive"))
    )
    (net (code "73") (name "Net-(D10-PadC)") (class "Default")
      (node (ref "D10") (pin "C") (pinfunction "C_C") (pintype "passive"))
      (node (ref "JP2") (pin "12") (pinfunction "12_12") (pintype "passive"))
    )
    (net (code "74") (name "Net-(D11-PadC)") (class "Default")
      (node (ref "D11") (pin "C") (pinfunction "C_C") (pintype "passive"))
      (node (ref "JP2") (pin "13") (pinfunction "13_13") (pintype "passive"))
    )
    (net (code "75") (name "Net-(D12-PadC)") (class "Default")
      (node (ref "D12") (pin "C") (pinfunction "C_C") (pintype "passive"))
      (node (ref "JP2") (pin "14") (pinfunction "14_14") (pintype "passive"))
    )
    (net (code "76") (name "Net-(D13-PadC)") (class "Default")
      (node (ref "D13") (pin "C") (pinfunction "C_C") (pintype "passive"))
      (node (ref "JP2") (pin "16") (pinfunction "16_16") (pintype "passive"))
    )
    (net (code "77") (name "Net-(D14-PadC)") (class "Default")
      (node (ref "D14") (pin "C") (pinfunction "C_C") (pintype "passive"))
      (node (ref "JP2") (pin "15") (pinfunction "15_15") (pintype "passive"))
    )
    (net (code "78") (name "Net-(IC2A-Q2)") (class "Default")
      (node (ref "IC2") (pin "6") (pinfunction "Q2_6") (pintype "output"))
      (node (ref "IC3") (pin "13") (pinfunction "I1_13") (pintype "input"))
    )
    (net (code "79") (name "Net-(IC2A-Q3)") (class "Default")
      (node (ref "IC2") (pin "7") (pinfunction "Q3_7") (pintype "output"))
      (node (ref "IC3") (pin "12") (pinfunction "I0_12") (pintype "input"))
    )
    (net (code "80") (name "Net-(IC2B-E)") (class "Default")
      (node (ref "IC2") (pin "15") (pinfunction "E_15") (pintype "input"))
      (node (ref "IC3") (pin "4") (pinfunction "O_4") (pintype "output"))
    )
    (net (code "81") (name "Net-(IC2B-Q1)") (class "Default")
      (node (ref "D15") (pin "A") (pinfunction "A_A") (pintype "passive"))
      (node (ref "IC2") (pin "11") (pinfunction "Q1_11") (pintype "output"))
    )
    (net (code "82") (name "Net-(IC2B-Q2)") (class "Default")
      (node (ref "IC2") (pin "10") (pinfunction "Q2_10") (pintype "output"))
      (node (ref "V2") (pin "1") (pinfunction "A_1") (pintype "input"))
    )
    (net (code "83") (name "Net-(IC2B-Q3)") (class "Default")
      (node (ref "IC2") (pin "9") (pinfunction "Q3_9") (pintype "output"))
      (node (ref "IC3") (pin "8") (pinfunction "I0_8") (pintype "input"))
      (node (ref "IC3") (pin "9") (pinfunction "I1_9") (pintype "input"))
    )
    (net (code "84") (name "Net-(IC3B-I1)") (class "Default")
      (node (ref "IC3") (pin "6") (pinfunction "I1_6") (pintype "input"))
      (node (ref "V2") (pin "4") (pinfunction "Y_4") (pintype "output"))
    )
    (net (code "85") (name "Net-(IC4-INT)") (class "Default")
      (node (ref "C6") (pin "1") (pinfunction "1_1") (pintype "passive"))
      (node (ref "IC4") (pin "16") (pinfunction "INT_16") (pintype "input"))
      (node (ref "R16") (pin "2") (pinfunction "2_2") (pintype "passive"))
      (node (ref "T3") (pin "3") (pinfunction "E_3") (pintype "passive"))
    )
    (net (code "86") (name "Net-(IC5A-~{CS})") (class "Default")
      (node (ref "D2") (pin "C") (pinfunction "C_C") (pintype "passive"))
      (node (ref "IC5") (pin "18") (pinfunction "~{CS}_18") (pintype "input"))
    )
    (net (code "87") (name "Net-(R17-Pad2)") (class "Default")
      (node (ref "R17") (pin "2") (pinfunction "2_2") (pintype "passive"))
      (node (ref "R18") (pin "1") (pinfunction "1_1") (pintype "passive"))
    )
    (net (code "88") (name "Net-(T1-B)") (class "Default")
      (node (ref "R21") (pin "1") (pinfunction "1_1") (pintype "passive"))
      (node (ref "T1") (pin "2") (pinfunction "B_2") (pintype "passive"))
    )
    (net (code "89") (name "Net-(T2-E)") (class "Default")
      (node (ref "JP3") (pin "18") (pinfunction "18_18") (pintype "passive"))
      (node (ref "T2") (pin "3") (pinfunction "E_3") (pintype "passive"))
    )
    (net (code "90") (name "Net-(V2E-A)") (class "Default")
      (node (ref "D15") (pin "C") (pinfunction "C_C") (pintype "passive"))
      (node (ref "D16") (pin "C") (pinfunction "C_C") (pintype "passive"))
      (node (ref "V2") (pin "5") (pinfunction "A_5") (pintype "input"))
    )
    (net (code "91") (name "Net-(V2F-A)") (class "Default")
      (node (ref "V2") (pin "10") (pinfunction "Y_10") (pintype "output"))
      (node (ref "V2") (pin "9") (pinfunction "A_9") (pintype "input"))
    )
    (net (code "92") (name "Net-(V2G-A)") (class "Default")
      (node (ref "R14") (pin "1") (pinfunction "1_1") (pintype "passive"))
      (node (ref "V2") (pin "11") (pinfunction "A_11") (pintype "input"))
      (node (ref "V2") (pin "12") (pinfunction "Y_12") (pintype "output"))
    )
    (net (code "93") (name "Net-(V2H-A)") (class "Default")
      (node (ref "R14") (pin "2") (pinfunction "2_2") (pintype "passive"))
      (node (ref "V2") (pin "13") (pinfunction "A_13") (pintype "input"))
    )
    (net (code "94") (name "RAM_CS") (class "Default")
      (node (ref "D2") (pin "A") (pinfunction "A_A") (pintype "passive"))
      (node (ref "IC2") (pin "5") (pinfunction "Q1_5") (pintype "output"))
      (node (ref "JP4") (pin "14") (pinfunction "14_14") (pintype "passive"))
      (node (ref "JP4") (pin "18") (pinfunction "18_18") (pintype "passive"))
    )
    (net (code "95") (name "RD_Z80") (class "Default")
      (node (ref "IC4") (pin "21") (pinfunction "RD_21") (pintype "output"))
      (node (ref "IC5") (pin "20") (pinfunction "~{OE}_20") (pintype "input"))
      (node (ref "JP4") (pin "15") (pinfunction "15_15") (pintype "passive"))
      (node (ref "JP6") (pin "4") (pinfunction "4_4") (pintype "passive"))
    )
    (net (code "96") (name "RESET") (class "Default")
      (node (ref "IC4") (pin "23") (pinfunction "BUSAK_23") (pintype "output"))
      (node (ref "IC4") (pin "26") (pinfunction "RESET_26") (pintype "input"))
    )
    (net (code "97") (name "RFSH") (class "Default")
      (node (ref "IC4") (pin "28") (pinfunction "RFSH_28") (pintype "output"))
    )
    (net (code "98") (name "STROBE_A") (class "Default")
      (node (ref "IC1") (pin "2") (pinfunction "ST_2") (pintype "input"))
      (node (ref "V2") (pin "6") (pinfunction "Y_6") (pintype "output"))
    )
    (net (code "99") (name "STROBE_B") (class "Default")
      (node (ref "IC1") (pin "14") (pinfunction "ST_14") (pintype "input"))
      (node (ref "V2") (pin "2") (pinfunction "Y_2") (pintype "output"))
    )
    (net (code "100") (name "VEE") (class "Default")
      (node (ref "DIS1") (pin "3") (pinfunction "VEE_3") (pintype "power_in"))
    )
    (net (code "101") (name "WE_Z80") (class "Default")
      (node (ref "IC4") (pin "22") (pinfunction "WR_22") (pintype "output"))
      (node (ref "IC5") (pin "21") (pinfunction "~{WE}_21") (pintype "input"))
      (node (ref "JP6") (pin "5") (pinfunction "5_5") (pintype "passive"))
    )
    (net (code "102") (name "WR") (class "Default")
      (node (ref "JP5") (pin "14") (pinfunction "14_14") (pintype "passive"))
    )
    (net (code "103") (name "unconnected-(C1-Pad1)") (class "Default")
      (node (ref "C1") (pin "1") (pinfunction "1_1") (pintype "passive"))
    )
    (net (code "104") (name "unconnected-(C1-Pad2)") (class "Default")
      (node (ref "C1") (pin "2") (pinfunction "2_2") (pintype "passive"))
    )
    (net (code "105") (name "unconnected-(C4-Pad1)") (class "Default")
      (node (ref "C4") (pin "1") (pinfunction "1_1") (pintype "passive"))
    )
    (net (code "106") (name "unconnected-(C4-Pad2)") (class "Default")
      (node (ref "C4") (pin "2") (pinfunction "2_2") (pintype "passive"))
    )
    (net (code "107") (name "unconnected-(D1-PadA)") (class "Default")
      (node (ref "D1") (pin "A") (pinfunction "A_A") (pintype "passive"))
    )
    (net (code "108") (name "unconnected-(D1-PadC)") (class "Default")
      (node (ref "D1") (pin "C") (pinfunction "C_C") (pintype "passive"))
    )
    (net (code "109") (name "unconnected-(D3-PadA)") (class "Default")
      (node (ref "D3") (pin "A") (pinfunction "A_A") (pintype "passive"))
    )
    (net (code "110") (name "unconnected-(D3-PadC)") (class "Default")
      (node (ref "D3") (pin "C") (pinfunction "C_C") (pintype "passive"))
    )
    (net (code "111") (name "unconnected-(D5-PadA)") (class "Default")
      (node (ref "D5") (pin "A") (pinfunction "A_A") (pintype "passive"))
    )
    (net (code "112") (name "unconnected-(D5-PadC)") (class "Default")
      (node (ref "D5") (pin "C") (pinfunction "C_C") (pintype "passive"))
    )
    (net (code "113") (name "unconnected-(DIS1-A-Pad17)") (class "Default")
      (node (ref "DIS1") (pin "17") (pinfunction "A_17") (pintype "passive"))
    )
    (net (code "114") (name "unconnected-(DIS1-C-Pad18)") (class "Default")
      (node (ref "DIS1") (pin "18") (pinfunction "C_18") (pintype "passive"))
    )
    (net (code "115") (name "unconnected-(DIS1-D0-Pad7)") (class "Default")
      (node (ref "DIS1") (pin "7") (pinfunction "D0_7") (pintype "input"))
    )
    (net (code "116") (name "unconnected-(DIS1-D1-Pad8)") (class "Default")
      (node (ref "DIS1") (pin "8") (pinfunction "D1_8") (pintype "input"))
    )
    (net (code "117") (name "unconnected-(DIS1-D2-Pad9)") (class "Default")
      (node (ref "DIS1") (pin "9") (pinfunction "D2_9") (pintype "input"))
    )
    (net (code "118") (name "unconnected-(DIS1-D3-Pad10)") (class "Default")
      (node (ref "DIS1") (pin "10") (pinfunction "D3_10") (pintype "input"))
    )
    (net (code "119") (name "unconnected-(DIS1-E-Pad6)") (class "Default")
      (node (ref "DIS1") (pin "6") (pinfunction "E_6") (pintype "input"))
    )
    (net (code "120") (name "unconnected-(DIS1-NC-Pad15)") (class "Default")
      (node (ref "DIS1") (pin "15") (pinfunction "NC_15") (pintype "no_connect"))
    )
    (net (code "121") (name "unconnected-(DIS1-NC-Pad16)") (class "Default")
      (node (ref "DIS1") (pin "16") (pinfunction "NC_16") (pintype "no_connect"))
    )
    (net (code "122") (name "unconnected-(DIS1-RS-Pad4)") (class "Default")
      (node (ref "DIS1") (pin "4") (pinfunction "RS_4") (pintype "input"))
    )
    (net (code "123") (name "unconnected-(IC1B-DIS-Pad15)") (class "Default")
      (node (ref "IC1") (pin "15") (pinfunction "DIS_15") (pintype "input"))
    )
    (net (code "124") (name "unconnected-(IC1B-MR-Pad13)") (class "Default")
      (node (ref "IC1") (pin "13") (pinfunction "MR_13") (pintype "input"))
    )
    (net (code "125") (name "unconnected-(JP3-Pad3)") (class "Default")
      (node (ref "JP3") (pin "3") (pinfunction "3_3") (pintype "passive"))
    )
    (net (code "126") (name "unconnected-(JP3-Pad4)") (class "Default")
      (node (ref "JP3") (pin "4") (pinfunction "4_4") (pintype "passive"))
    )
    (net (code "127") (name "unconnected-(R1-Pad1)") (class "Default")
      (node (ref "R1") (pin "1") (pinfunction "1_1") (pintype "passive"))
    )
    (net (code "128") (name "unconnected-(R1-Pad2)") (class "Default")
      (node (ref "R1") (pin "2") (pinfunction "2_2") (pintype "passive"))
    )
    (net (code "129") (name "unconnected-(R5-Pad1)") (class "Default")
      (node (ref "R5") (pin "1") (pinfunction "1_1") (pintype "passive"))
    )
    (net (code "130") (name "unconnected-(R5-Pad2)") (class "Default")
      (node (ref "R5") (pin "2") (pinfunction "2_2") (pintype "passive"))
    )
    (net (code "131") (name "unconnected-(R9-Pad2)") (class "Default")
      (node (ref "R9") (pin "2") (pinfunction "2_2") (pintype "passive"))
    )
  )
)
